# almost_smart_thermostat_v01.net
KiCad netlist of a schematic drawn in EAGLE
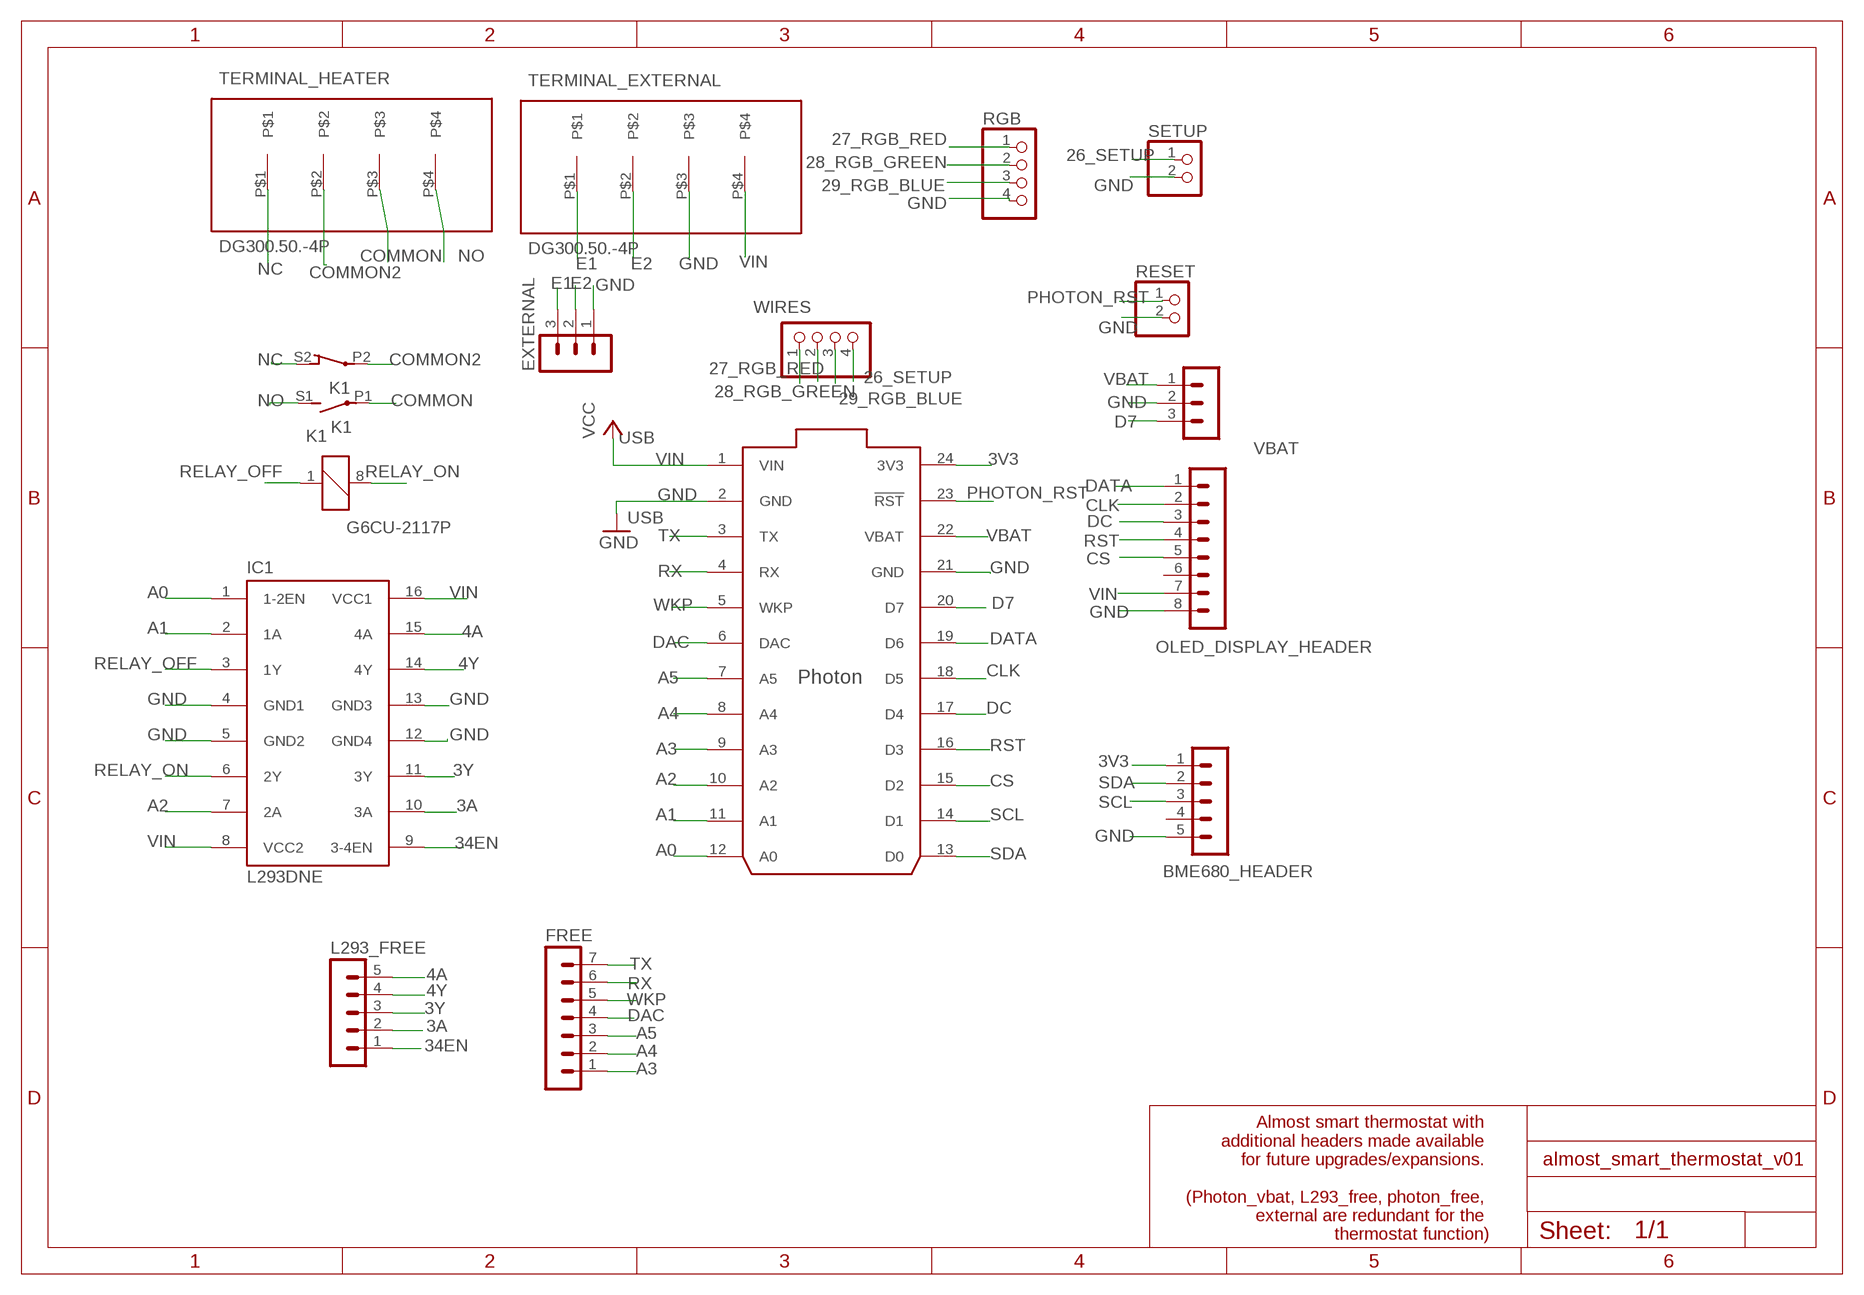
[diagram p0: schematic, sheet 1]

(export (version "E")
  (design (tool "Eeschema 10.0.6"))
  (components
    (comp (ref "BME680_HEADER")
      (value "MA05-1")
      (footprint "eagle-import:MA05-1")
      (libsource (lib "eagle-import") (part "MA05-1"))
    )
    (comp (ref "EXTERNAL")
      (value "MA03-1")
      (footprint "eagle-import:MA03-1")
      (libsource (lib "eagle-import") (part "MA03-1"))
    )
    (comp (ref "FREE")
      (value "MA07-1")
      (footprint "eagle-import:MA07-1")
      (libsource (lib "eagle-import") (part "MA07-1"))
    )
    (comp (ref "IC1")
      (value "L293DNE")
      (footprint "eagle-import:DIL16")
      (libsource (lib "eagle-import") (part "L293D"))
    )
    (comp (ref "K1")
      (value "G6CU-2117P")
      (footprint "eagle-import:G6C-2117P")
      (libsource (lib "eagle-import") (part "G6C-2117P"))
    )
    (comp (ref "L293_FREE")
      (value "MA05-1")
      (footprint "eagle-import:MA05-1")
      (libsource (lib "eagle-import") (part "MA05-1"))
    )
    (comp (ref "OLED_DISPLAY_HEADER")
      (value "MA08-1")
      (footprint "eagle-import:MA08-1")
      (libsource (lib "eagle-import") (part "MA08-1"))
    )
    (comp (ref "RESET")
      (value "PINHD-1X2")
      (footprint "eagle-import:1X02")
      (libsource (lib "eagle-import") (part "PINHD-1X2"))
    )
    (comp (ref "RGB")
      (value "PINHD-1X4")
      (footprint "eagle-import:1X04")
      (libsource (lib "eagle-import") (part "PINHD-1X4"))
    )
    (comp (ref "SETUP")
      (value "PINHD-1X2")
      (footprint "eagle-import:1X02")
      (libsource (lib "eagle-import") (part "PINHD-1X2"))
    )
    (comp (ref "TERMINAL_EXTERNAL")
      (value "DG300.50.-4P")
      (footprint "eagle-import:DG300-5.0-4P")
      (libsource (lib "eagle-import") (part "DG300.50.-4P"))
    )
    (comp (ref "TERMINAL_HEATER")
      (value "DG300.50.-4P")
      (footprint "eagle-import:DG300-5.0-4P")
      (libsource (lib "eagle-import") (part "DG300.50.-4P"))
    )
    (comp (ref "U$1")
      (value "PHOTON_WITH_HEADERS")
      (footprint "eagle-import:PHOTON")
      (libsource (lib "eagle-import") (part "PHOTON_WITH_HEADERS"))
    )
    (comp (ref "VBAT")
      (value "MA03-1")
      (footprint "eagle-import:MA03-1")
      (libsource (lib "eagle-import") (part "MA03-1"))
    )
    (comp (ref "WIRES")
      (value "PINHD-1X4")
      (footprint "eagle-import:1X04")
      (libsource (lib "eagle-import") (part "PINHD-1X4"))
    )
  )
  (nets
    (net (code "1") (name "/3A") (class "Default")
      (node (ref "IC1") (pin "10") (pinfunction "3A_10") (pintype "input"))
      (node (ref "L293_FREE") (pin "2") (pinfunction "2_2") (pintype "passive"))
    )
    (net (code "2") (name "/3V3") (class "Default")
      (node (ref "BME680_HEADER") (pin "1") (pinfunction "1_1") (pintype "passive"))
      (node (ref "U$1") (pin "24") (pinfunction "3V3_24") (pintype "power_in"))
    )
    (net (code "3") (name "/3Y") (class "Default")
      (node (ref "IC1") (pin "11") (pinfunction "3Y_11") (pintype "output"))
      (node (ref "L293_FREE") (pin "3") (pinfunction "3_3") (pintype "passive"))
    )
    (net (code "4") (name "/4A") (class "Default")
      (node (ref "IC1") (pin "15") (pinfunction "4A_15") (pintype "input"))
      (node (ref "L293_FREE") (pin "5") (pinfunction "5_5") (pintype "passive"))
    )
    (net (code "5") (name "/4Y") (class "Default")
      (node (ref "IC1") (pin "14") (pinfunction "4Y_14") (pintype "output"))
      (node (ref "L293_FREE") (pin "4") (pinfunction "4_4") (pintype "passive"))
    )
    (net (code "6") (name "/26_SETUP") (class "Default")
      (node (ref "SETUP") (pin "1") (pinfunction "1_1") (pintype "passive"))
      (node (ref "WIRES") (pin "4") (pinfunction "4_4") (pintype "passive"))
    )
    (net (code "7") (name "/27_RGB_RED") (class "Default")
      (node (ref "RGB") (pin "1") (pinfunction "1_1") (pintype "passive"))
      (node (ref "WIRES") (pin "1") (pinfunction "1_1") (pintype "passive"))
    )
    (net (code "8") (name "/28_RGB_GREEN") (class "Default")
      (node (ref "RGB") (pin "2") (pinfunction "2_2") (pintype "passive"))
      (node (ref "WIRES") (pin "2") (pinfunction "2_2") (pintype "passive"))
    )
    (net (code "9") (name "/29_RGB_BLUE") (class "Default")
      (node (ref "RGB") (pin "3") (pinfunction "3_3") (pintype "passive"))
      (node (ref "WIRES") (pin "3") (pinfunction "3_3") (pintype "passive"))
    )
    (net (code "10") (name "/34EN") (class "Default")
      (node (ref "IC1") (pin "9") (pinfunction "3-4EN_9") (pintype "input"))
      (node (ref "L293_FREE") (pin "1") (pinfunction "1_1") (pintype "passive"))
    )
    (net (code "11") (name "/A0") (class "Default")
      (node (ref "IC1") (pin "1") (pinfunction "1-2EN_1") (pintype "input"))
      (node (ref "U$1") (pin "12") (pinfunction "A0_12") (pintype "bidirectional"))
    )
    (net (code "12") (name "/A1") (class "Default")
      (node (ref "IC1") (pin "2") (pinfunction "1A_2") (pintype "input"))
      (node (ref "U$1") (pin "11") (pinfunction "A1_11") (pintype "bidirectional"))
    )
    (net (code "13") (name "/A2") (class "Default")
      (node (ref "IC1") (pin "7") (pinfunction "2A_7") (pintype "input"))
      (node (ref "U$1") (pin "10") (pinfunction "A2_10") (pintype "bidirectional"))
    )
    (net (code "14") (name "/A3") (class "Default")
      (node (ref "FREE") (pin "1") (pinfunction "1_1") (pintype "passive"))
      (node (ref "U$1") (pin "9") (pinfunction "A3_9") (pintype "bidirectional"))
    )
    (net (code "15") (name "/A4") (class "Default")
      (node (ref "FREE") (pin "2") (pinfunction "2_2") (pintype "passive"))
      (node (ref "U$1") (pin "8") (pinfunction "A4_8") (pintype "bidirectional"))
    )
    (net (code "16") (name "/A5") (class "Default")
      (node (ref "FREE") (pin "3") (pinfunction "3_3") (pintype "passive"))
      (node (ref "U$1") (pin "7") (pinfunction "A5_7") (pintype "bidirectional"))
    )
    (net (code "17") (name "/CLK") (class "Default")
      (node (ref "OLED_DISPLAY_HEADER") (pin "2") (pinfunction "2_2") (pintype "passive"))
      (node (ref "U$1") (pin "18") (pinfunction "D5_18") (pintype "bidirectional"))
    )
    (net (code "18") (name "/COMMON") (class "Default")
      (node (ref "K1") (pin "P1") (pinfunction "P_P1") (pintype "passive"))
      (node (ref "TERMINAL_HEATER") (pin "P$3") (pinfunction "P$3_P$3") (pintype "bidirectional"))
    )
    (net (code "19") (name "/COMMON2") (class "Default")
      (node (ref "K1") (pin "P2") (pinfunction "P_P2") (pintype "passive"))
      (node (ref "TERMINAL_HEATER") (pin "P$2") (pinfunction "P$2_P$2") (pintype "bidirectional"))
    )
    (net (code "20") (name "/CS") (class "Default")
      (node (ref "OLED_DISPLAY_HEADER") (pin "5") (pinfunction "5_5") (pintype "passive"))
      (node (ref "U$1") (pin "15") (pinfunction "D2_15") (pintype "bidirectional"))
    )
    (net (code "21") (name "/D7") (class "Default")
      (node (ref "U$1") (pin "20") (pinfunction "D7_20") (pintype "bidirectional"))
      (node (ref "VBAT") (pin "3") (pinfunction "3_3") (pintype "passive"))
    )
    (net (code "22") (name "/DAC") (class "Default")
      (node (ref "FREE") (pin "4") (pinfunction "4_4") (pintype "passive"))
      (node (ref "U$1") (pin "6") (pinfunction "DAC_6") (pintype "bidirectional"))
    )
    (net (code "23") (name "/DATA") (class "Default")
      (node (ref "OLED_DISPLAY_HEADER") (pin "1") (pinfunction "1_1") (pintype "passive"))
      (node (ref "U$1") (pin "19") (pinfunction "D6_19") (pintype "bidirectional"))
    )
    (net (code "24") (name "/DC") (class "Default")
      (node (ref "OLED_DISPLAY_HEADER") (pin "3") (pinfunction "3_3") (pintype "passive"))
      (node (ref "U$1") (pin "17") (pinfunction "D4_17") (pintype "bidirectional"))
    )
    (net (code "25") (name "/E1") (class "Default")
      (node (ref "EXTERNAL") (pin "3") (pinfunction "3_3") (pintype "passive"))
      (node (ref "TERMINAL_EXTERNAL") (pin "P$1") (pinfunction "P$1_P$1") (pintype "bidirectional"))
    )
    (net (code "26") (name "/E2") (class "Default")
      (node (ref "EXTERNAL") (pin "2") (pinfunction "2_2") (pintype "passive"))
      (node (ref "TERMINAL_EXTERNAL") (pin "P$2") (pinfunction "P$2_P$2") (pintype "bidirectional"))
    )
    (net (code "27") (name "/NC") (class "Default")
      (node (ref "K1") (pin "S2") (pinfunction "O_S2") (pintype "passive"))
      (node (ref "TERMINAL_HEATER") (pin "P$1") (pinfunction "P$1_P$1") (pintype "bidirectional"))
    )
    (net (code "28") (name "/NO") (class "Default")
      (node (ref "K1") (pin "S1") (pinfunction "S_S1") (pintype "passive"))
      (node (ref "TERMINAL_HEATER") (pin "P$4") (pinfunction "P$4_P$4") (pintype "bidirectional"))
    )
    (net (code "29") (name "/PHOTON_RST") (class "Default")
      (node (ref "RESET") (pin "1") (pinfunction "1_1") (pintype "passive"))
      (node (ref "U$1") (pin "23") (pinfunction "~{RST}_23") (pintype "bidirectional"))
    )
    (net (code "30") (name "/RELAY_OFF") (class "Default")
      (node (ref "IC1") (pin "3") (pinfunction "1Y_3") (pintype "output"))
      (node (ref "K1") (pin "1") (pinfunction "1_1") (pintype "passive"))
    )
    (net (code "31") (name "/RELAY_ON") (class "Default")
      (node (ref "IC1") (pin "6") (pinfunction "2Y_6") (pintype "output"))
      (node (ref "K1") (pin "8") (pinfunction "2_8") (pintype "passive"))
    )
    (net (code "32") (name "/RST") (class "Default")
      (node (ref "OLED_DISPLAY_HEADER") (pin "4") (pinfunction "4_4") (pintype "passive"))
      (node (ref "U$1") (pin "16") (pinfunction "D3_16") (pintype "bidirectional"))
    )
    (net (code "33") (name "/RX") (class "Default")
      (node (ref "FREE") (pin "6") (pinfunction "6_6") (pintype "passive"))
      (node (ref "U$1") (pin "4") (pinfunction "RX_4") (pintype "bidirectional"))
    )
    (net (code "34") (name "/SCL") (class "Default")
      (node (ref "BME680_HEADER") (pin "3") (pinfunction "3_3") (pintype "passive"))
      (node (ref "U$1") (pin "14") (pinfunction "D1_14") (pintype "bidirectional"))
    )
    (net (code "35") (name "/SDA") (class "Default")
      (node (ref "BME680_HEADER") (pin "2") (pinfunction "2_2") (pintype "passive"))
      (node (ref "U$1") (pin "13") (pinfunction "D0_13") (pintype "bidirectional"))
    )
    (net (code "36") (name "/TX") (class "Default")
      (node (ref "FREE") (pin "7") (pinfunction "7_7") (pintype "passive"))
      (node (ref "U$1") (pin "3") (pinfunction "TX_3") (pintype "bidirectional"))
    )
    (net (code "37") (name "/VBAT") (class "Default")
      (node (ref "U$1") (pin "22") (pinfunction "VBAT_22") (pintype "power_in"))
      (node (ref "VBAT") (pin "1") (pinfunction "1_1") (pintype "passive"))
    )
    (net (code "38") (name "/WKP") (class "Default")
      (node (ref "FREE") (pin "5") (pinfunction "5_5") (pintype "passive"))
      (node (ref "U$1") (pin "5") (pinfunction "WKP_5") (pintype "bidirectional"))
    )
    (net (code "39") (name "GND") (class "Default")
      (node (ref "BME680_HEADER") (pin "5") (pinfunction "5_5") (pintype "passive"))
      (node (ref "EXTERNAL") (pin "1") (pinfunction "1_1") (pintype "passive"))
      (node (ref "IC1") (pin "12") (pinfunction "GND4_12") (pintype "power_in"))
      (node (ref "IC1") (pin "13") (pinfunction "GND3_13") (pintype "power_in"))
      (node (ref "IC1") (pin "4") (pinfunction "GND1_4") (pintype "power_in"))
      (node (ref "IC1") (pin "5") (pinfunction "GND2_5") (pintype "power_in"))
      (node (ref "OLED_DISPLAY_HEADER") (pin "8") (pinfunction "8_8") (pintype "passive"))
      (node (ref "RESET") (pin "2") (pinfunction "2_2") (pintype "passive"))
      (node (ref "RGB") (pin "4") (pinfunction "4_4") (pintype "passive"))
      (node (ref "SETUP") (pin "2") (pinfunction "2_2") (pintype "passive"))
      (node (ref "TERMINAL_EXTERNAL") (pin "P$3") (pinfunction "P$3_P$3") (pintype "bidirectional"))
      (node (ref "U$1") (pin "2") (pinfunction "GND_2") (pintype "power_in"))
      (node (ref "U$1") (pin "21") (pinfunction "GND_21") (pintype "power_in"))
      (node (ref "VBAT") (pin "2") (pinfunction "2_2") (pintype "passive"))
    )
    (net (code "40") (name "VCC") (class "Default")
      (node (ref "IC1") (pin "16") (pinfunction "VCC1_16") (pintype "power_in"))
      (node (ref "IC1") (pin "8") (pinfunction "VCC2_8") (pintype "power_in"))
      (node (ref "OLED_DISPLAY_HEADER") (pin "7") (pinfunction "7_7") (pintype "passive"))
      (node (ref "TERMINAL_EXTERNAL") (pin "P$4") (pinfunction "P$4_P$4") (pintype "bidirectional"))
      (node (ref "U$1") (pin "1") (pinfunction "VIN_1") (pintype "power_in"))
    )
    (net (code "41") (name "unconnected-(BME680_HEADER-Pad4)") (class "Default")
      (node (ref "BME680_HEADER") (pin "4") (pinfunction "4_4") (pintype "passive"))
    )
    (net (code "42") (name "unconnected-(OLED_DISPLAY_HEADER-Pad6)") (class "Default")
      (node (ref "OLED_DISPLAY_HEADER") (pin "6") (pinfunction "6_6") (pintype "passive"))
    )
  )
)
